# 2024-SS-ZT-1.net
KiCad netlist of a schematic drawn in EasyEDA Pro
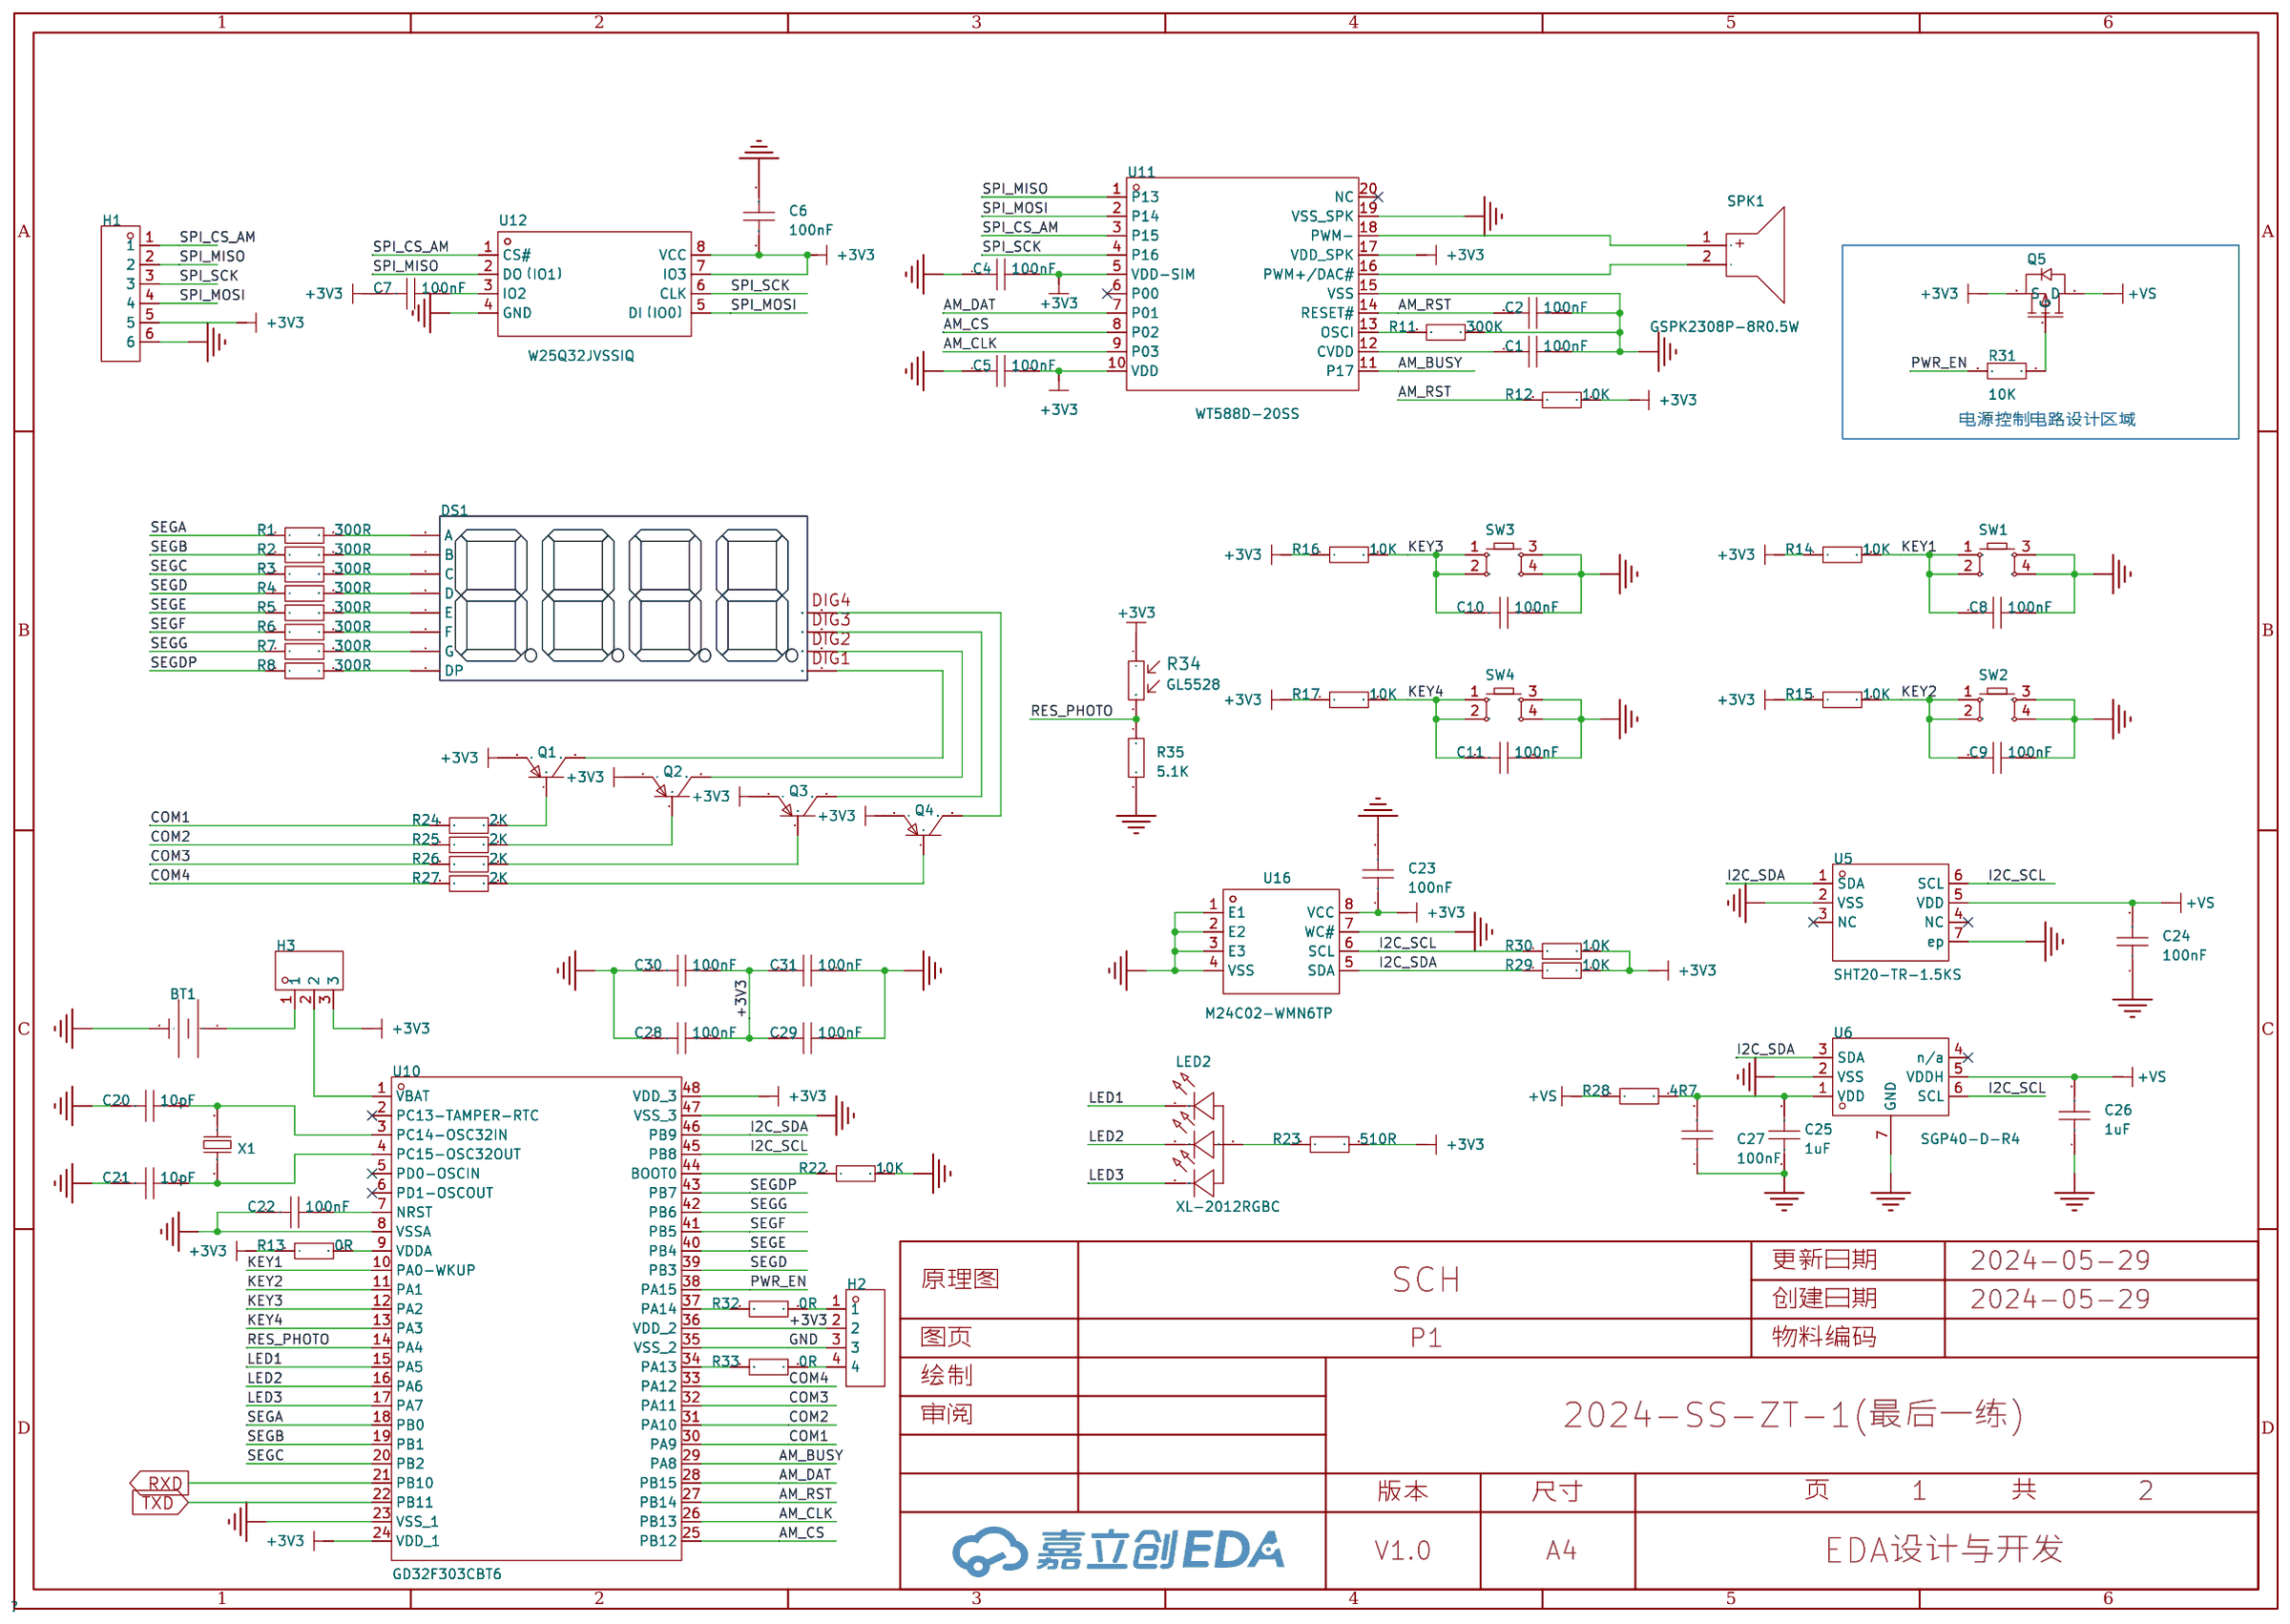
[diagram p0: P1]
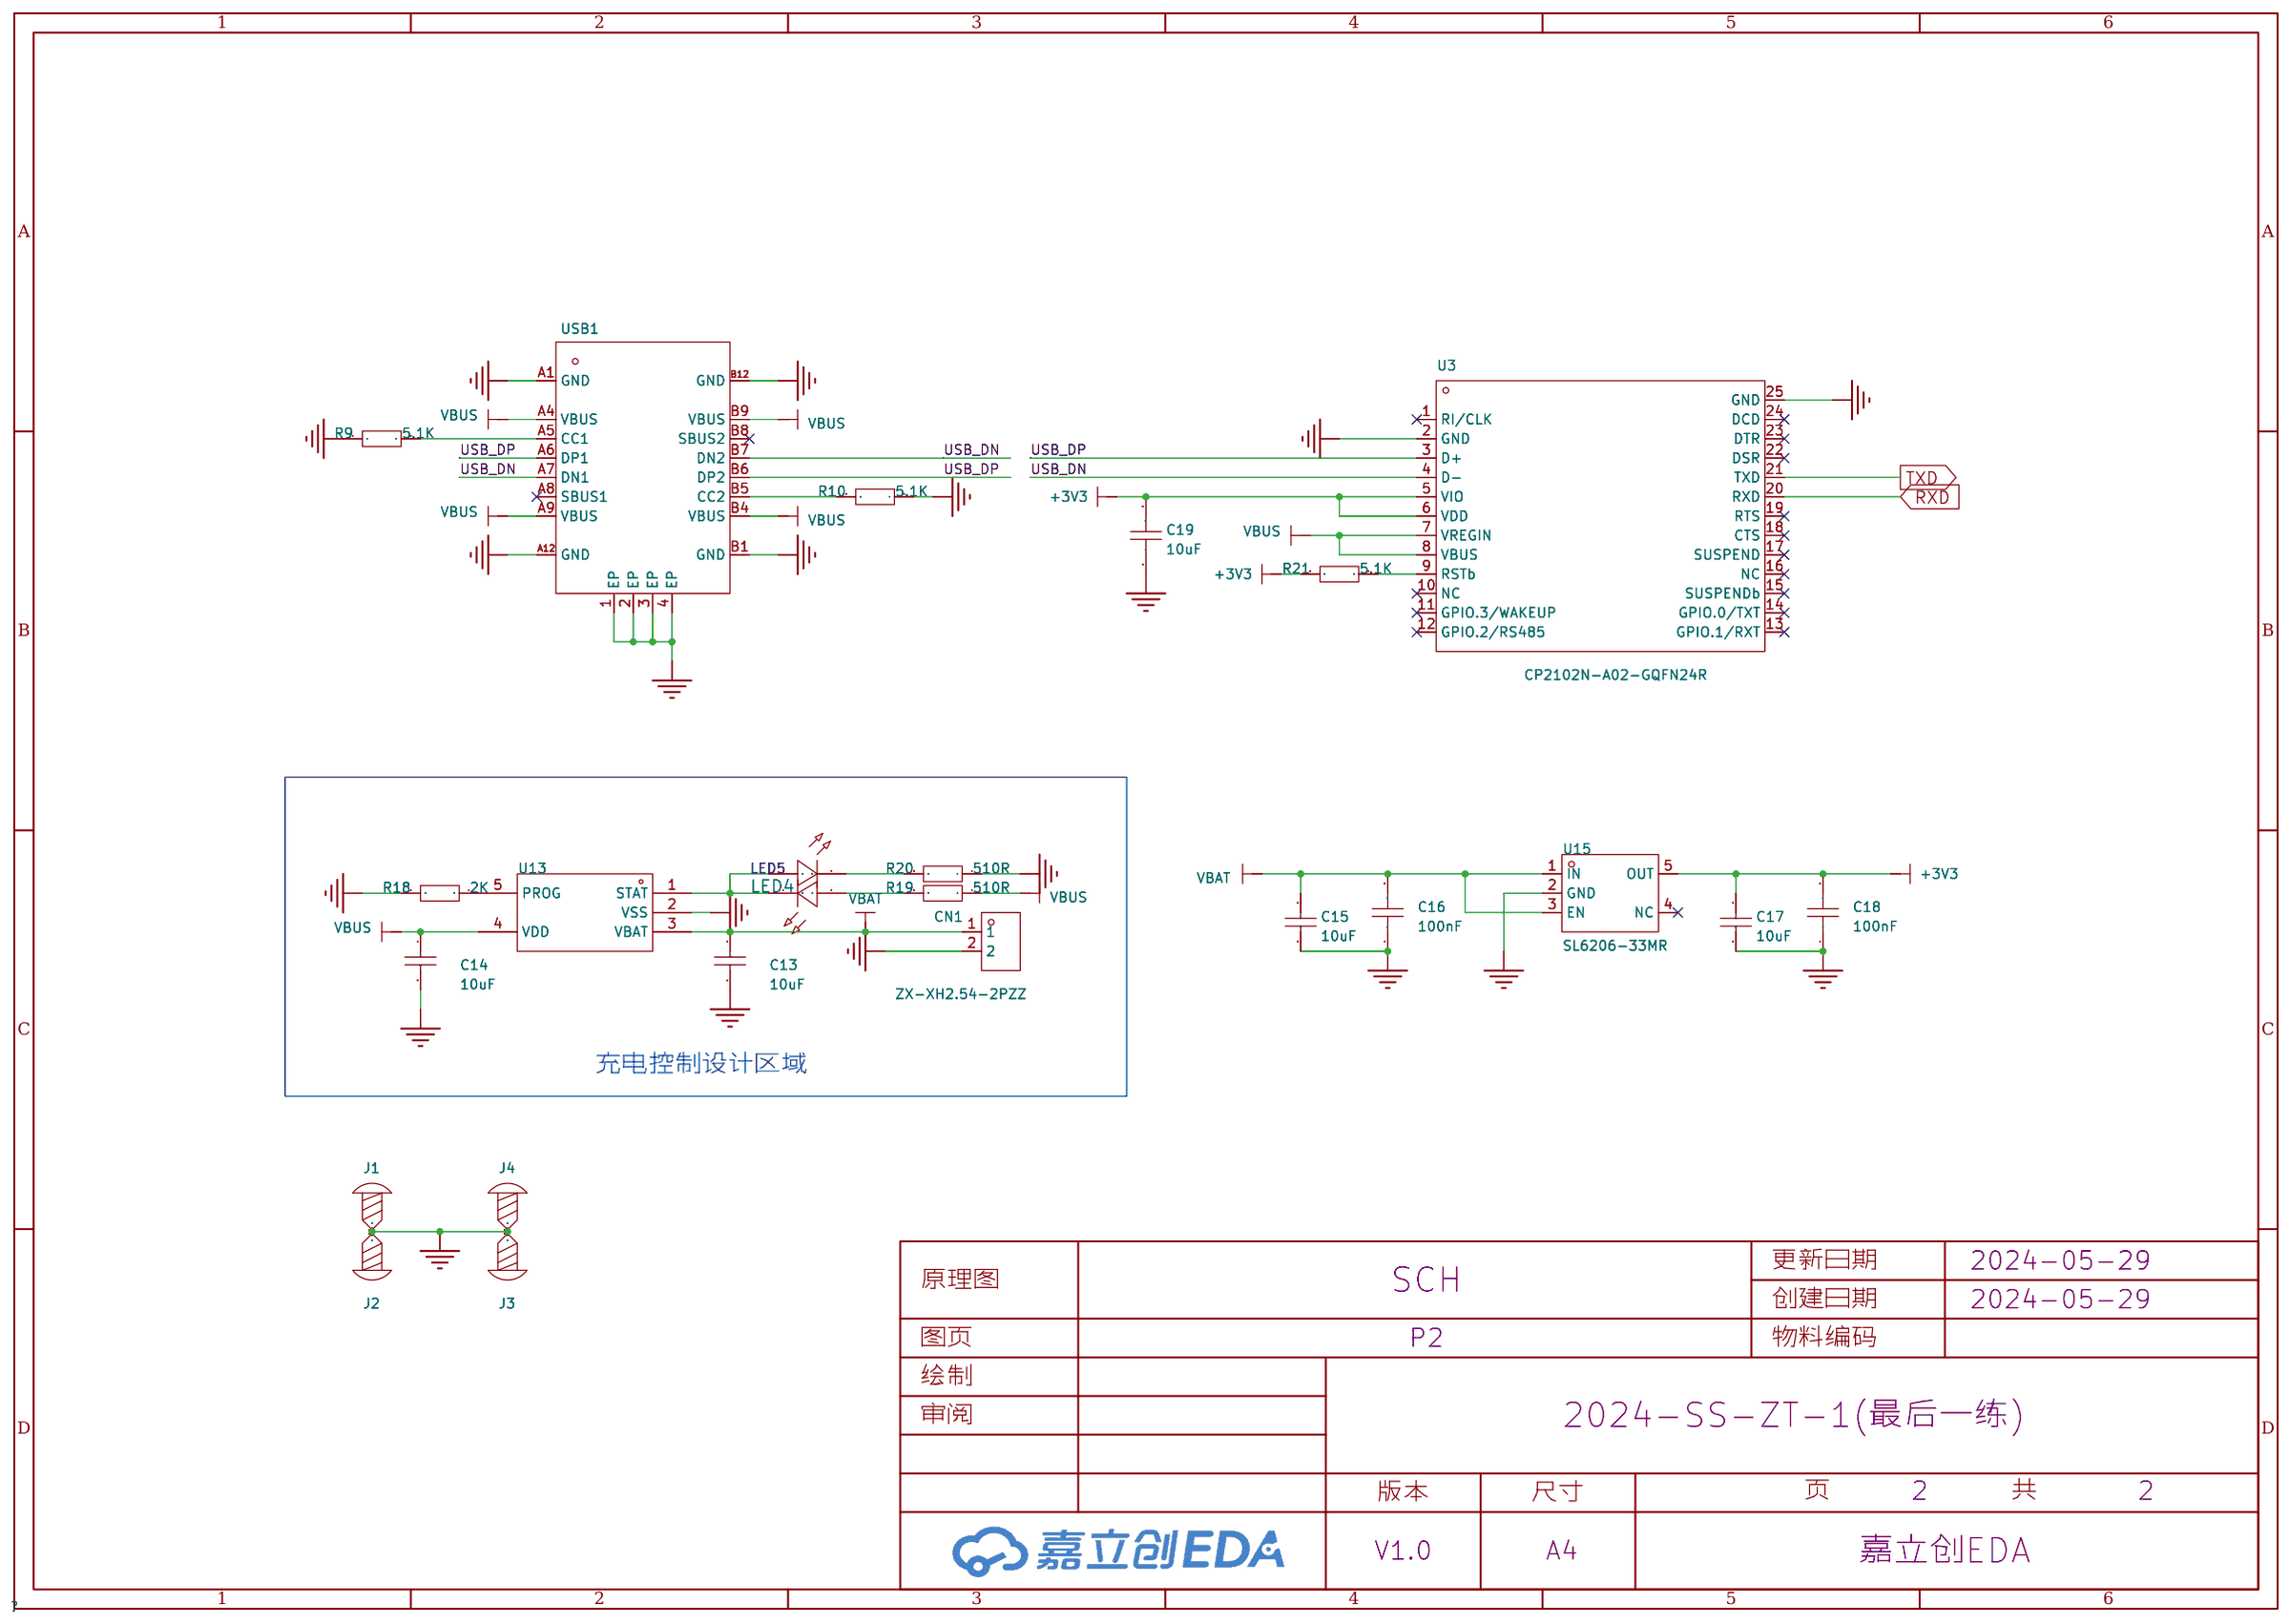
[diagram p1: P2]

(export (version "E")
  (design (tool "Eeschema 10.0.6"))
  (components
    (comp (ref "BT1")
      (value "BS-12-B3AA003")
      (footprint "easyedapro:BAT-SMD_BS-12-B3AA011")
      (description "连接器类型:电池底座;适用电池规格:CR1220;工作温度范围:-25°C~+85°C;")
      (fields (field (name "Manufacturer") "MYOUNG(美阳)"))
      (libsource (lib "easyedapro") (part "BS-12-B3AA003"))
    )
    (comp (ref "C1")
      (value "100nF")
      (footprint "easyedapro:C0805")
      (libsource (lib "easyedapro") (part "CapAcitance"))
    )
    (comp (ref "C2")
      (value "100nF")
      (footprint "easyedapro:C0805")
      (libsource (lib "easyedapro") (part "CapAcitance"))
    )
    (comp (ref "C4")
      (value "100nF")
      (footprint "easyedapro:C0805")
      (libsource (lib "easyedapro") (part "CapAcitance"))
    )
    (comp (ref "C5")
      (value "100nF")
      (footprint "easyedapro:C0805")
      (libsource (lib "easyedapro") (part "CapAcitance"))
    )
    (comp (ref "C6")
      (value "100nF")
      (footprint "easyedapro:C0805")
      (libsource (lib "easyedapro") (part "CapAcitance"))
    )
    (comp (ref "C7")
      (value "100nF")
      (footprint "easyedapro:C0805")
      (libsource (lib "easyedapro") (part "CapAcitance"))
    )
    (comp (ref "C8")
      (value "100nF")
      (footprint "easyedapro:C0805")
      (libsource (lib "easyedapro") (part "CapAcitance"))
    )
    (comp (ref "C9")
      (value "100nF")
      (footprint "easyedapro:C0805")
      (libsource (lib "easyedapro") (part "CapAcitance"))
    )
    (comp (ref "C10")
      (value "100nF")
      (footprint "easyedapro:C0805")
      (libsource (lib "easyedapro") (part "CapAcitance"))
    )
    (comp (ref "C11")
      (value "100nF")
      (footprint "easyedapro:C0805")
      (libsource (lib "easyedapro") (part "CapAcitance"))
    )
    (comp (ref "C20")
      (value "10pF")
      (footprint "easyedapro:C0805")
      (libsource (lib "easyedapro") (part "CapAcitance"))
    )
    (comp (ref "C21")
      (value "10pF")
      (footprint "easyedapro:C0805")
      (libsource (lib "easyedapro") (part "CapAcitance"))
    )
    (comp (ref "C22")
      (value "100nF")
      (footprint "easyedapro:C0805")
      (libsource (lib "easyedapro") (part "CapAcitance"))
    )
    (comp (ref "C23")
      (value "100nF")
      (footprint "easyedapro:C0805")
      (libsource (lib "easyedapro") (part "CapAcitance"))
    )
    (comp (ref "C24")
      (value "100nF")
      (footprint "easyedapro:C0805")
      (libsource (lib "easyedapro") (part "CapAcitance"))
    )
    (comp (ref "C25")
      (value "1uF")
      (footprint "easyedapro:C0805")
      (libsource (lib "easyedapro") (part "CapAcitance"))
    )
    (comp (ref "C26")
      (value "1uF")
      (footprint "easyedapro:C0805")
      (libsource (lib "easyedapro") (part "CapAcitance"))
    )
    (comp (ref "C27")
      (value "100nF")
      (footprint "easyedapro:C0805")
      (libsource (lib "easyedapro") (part "CapAcitance"))
    )
    (comp (ref "C28")
      (value "100nF")
      (footprint "easyedapro:C0805")
      (libsource (lib "easyedapro") (part "CapAcitance"))
    )
    (comp (ref "C29")
      (value "100nF")
      (footprint "easyedapro:C0805")
      (libsource (lib "easyedapro") (part "CapAcitance"))
    )
    (comp (ref "C30")
      (value "100nF")
      (footprint "easyedapro:C0805")
      (libsource (lib "easyedapro") (part "CapAcitance"))
    )
    (comp (ref "C31")
      (value "100nF")
      (footprint "easyedapro:C0805")
      (libsource (lib "easyedapro") (part "CapAcitance"))
    )
    (comp (ref "DS1")
      (value "~")
      (footprint "easyedapro:LED-SEG-TH_FJ5461AH")
      (libsource (lib "easyedapro") (part "LED_SEG_TH_0.56x4"))
    )
    (comp (ref "H1")
      (value "~")
      (footprint "easyedapro:HDR-TH_6P-P2.54-V-F")
      (libsource (lib "easyedapro") (part "Header-Female-2.54_1x6"))
    )
    (comp (ref "H2")
      (value "~")
      (footprint "easyedapro:HDR-TH_4P-P2.54-V-F")
      (libsource (lib "easyedapro") (part "2.54-1*4P母"))
    )
    (comp (ref "H3")
      (value "Jumper3")
      (footprint "easyedapro:HDR-TH_3P-P2.54-V-M-A")
      (libsource (lib "easyedapro") (part "JUMPER3"))
    )
    (comp (ref "LED2")
      (value "XL-2012RGBC")
      (footprint "easyedapro:LED-SMD_4P-L2.0-W1.3-BR")
      (fields (field (name "Manufacturer") "XINGLIGHT(成兴光)"))
      (libsource (lib "easyedapro") (part "XL-2012RGBC"))
    )
    (comp (ref "Q1")
      (value "~")
      (footprint "easyedapro:S8550P_SOT")
      (libsource (lib "easyedapro") (part "PNP"))
    )
    (comp (ref "Q2")
      (value "~")
      (footprint "easyedapro:S8550P_SOT")
      (libsource (lib "easyedapro") (part "PNP"))
    )
    (comp (ref "Q3")
      (value "~")
      (footprint "easyedapro:S8550P_SOT")
      (libsource (lib "easyedapro") (part "PNP"))
    )
    (comp (ref "Q4")
      (value "~")
      (footprint "easyedapro:S8550P_SOT")
      (libsource (lib "easyedapro") (part "PNP"))
    )
    (comp (ref "Q5")
      (value "~")
      (footprint "easyedapro:AO3401A_SOT-23-3")
      (libsource (lib "easyedapro") (part "P_MOS"))
    )
    (comp (ref "R1") (value "300R") (footprint "easyedapro:R0805") (libsource (lib "easyedapro") (part "电阻")))
    (comp (ref "R2") (value "300R") (footprint "easyedapro:R0805") (libsource (lib "easyedapro") (part "电阻")))
    (comp (ref "R3") (value "300R") (footprint "easyedapro:R0805") (libsource (lib "easyedapro") (part "电阻")))
    (comp (ref "R4") (value "300R") (footprint "easyedapro:R0805") (libsource (lib "easyedapro") (part "电阻")))
    (comp (ref "R5") (value "300R") (footprint "easyedapro:R0805") (libsource (lib "easyedapro") (part "电阻")))
    (comp (ref "R6") (value "300R") (footprint "easyedapro:R0805") (libsource (lib "easyedapro") (part "电阻")))
    (comp (ref "R7") (value "300R") (footprint "easyedapro:R0805") (libsource (lib "easyedapro") (part "电阻")))
    (comp (ref "R8") (value "300R") (footprint "easyedapro:R0805") (libsource (lib "easyedapro") (part "电阻")))
    (comp (ref "R11")
      (value "300K")
      (footprint "easyedapro:R0805")
      (libsource (lib "easyedapro") (part "电阻"))
    )
    (comp (ref "R12") (value "10K") (footprint "easyedapro:R0805") (libsource (lib "easyedapro") (part "电阻")))
    (comp (ref "R13") (value "0R") (footprint "easyedapro:R0805") (libsource (lib "easyedapro") (part "电阻")))
    (comp (ref "R14") (value "10K") (footprint "easyedapro:R0805") (libsource (lib "easyedapro") (part "电阻")))
    (comp (ref "R15") (value "10K") (footprint "easyedapro:R0805") (libsource (lib "easyedapro") (part "电阻")))
    (comp (ref "R16") (value "10K") (footprint "easyedapro:R0805") (libsource (lib "easyedapro") (part "电阻")))
    (comp (ref "R17") (value "10K") (footprint "easyedapro:R0805") (libsource (lib "easyedapro") (part "电阻")))
    (comp (ref "R22") (value "10K") (footprint "easyedapro:R0805") (libsource (lib "easyedapro") (part "电阻")))
    (comp (ref "R23")
      (value "510R")
      (footprint "easyedapro:R0805")
      (libsource (lib "easyedapro") (part "电阻"))
    )
    (comp (ref "R24") (value "2K") (footprint "easyedapro:R0805") (libsource (lib "easyedapro") (part "电阻")))
    (comp (ref "R25") (value "2K") (footprint "easyedapro:R0805") (libsource (lib "easyedapro") (part "电阻")))
    (comp (ref "R26") (value "2K") (footprint "easyedapro:R0805") (libsource (lib "easyedapro") (part "电阻")))
    (comp (ref "R27") (value "2K") (footprint "easyedapro:R0805") (libsource (lib "easyedapro") (part "电阻")))
    (comp (ref "R28") (value "4R7") (footprint "easyedapro:R0805") (libsource (lib "easyedapro") (part "电阻")))
    (comp (ref "R29") (value "10K") (footprint "easyedapro:R0805") (libsource (lib "easyedapro") (part "电阻")))
    (comp (ref "R30") (value "10K") (footprint "easyedapro:R0805") (libsource (lib "easyedapro") (part "电阻")))
    (comp (ref "R31") (value "10K") (footprint "easyedapro:R0805") (libsource (lib "easyedapro") (part "电阻")))
    (comp (ref "R32") (value "0R") (footprint "easyedapro:R0805") (libsource (lib "easyedapro") (part "电阻")))
    (comp (ref "R33") (value "0R") (footprint "easyedapro:R0805") (libsource (lib "easyedapro") (part "电阻")))
    (comp (ref "R34")
      (value "GL5528")
      (footprint "easyedapro:RES-TH_L5.1-W4.3-P3.40-D0.5")
      (description "暗电阻:1MΩ;亮电阻 @ 10Lux:8kΩ~20kΩ;光谱峰值(波长):540nm;")
      (fields (field (name "Manufacturer") "森霸"))
      (libsource (lib "easyedapro") (part "GL5528"))
    )
    (comp (ref "R35")
      (value "5.1K")
      (footprint "easyedapro:R0805")
      (libsource (lib "easyedapro") (part "电阻"))
    )
    (comp (ref "SPK1")
      (value "GSPK2308P-8R0.5W")
      (footprint "easyedapro:SPK-TH_BD23.0-P10.00-D0.8-L-RD")
      (fields (field (name "Manufacturer") "INGHAi(赢海)"))
      (libsource (lib "easyedapro") (part "GSPK2308P-8R0.5W"))
    )
    (comp (ref "SW1")
      (value "~")
      (footprint "easyedapro:Key_SMD_12x12x7.3")
      (libsource (lib "easyedapro") (part "轻触按键"))
    )
    (comp (ref "SW2")
      (value "~")
      (footprint "easyedapro:Key_SMD_12x12x7.3")
      (libsource (lib "easyedapro") (part "轻触按键"))
    )
    (comp (ref "SW3")
      (value "~")
      (footprint "easyedapro:Key_SMD_12x12x7.3")
      (libsource (lib "easyedapro") (part "轻触按键"))
    )
    (comp (ref "SW4")
      (value "~")
      (footprint "easyedapro:Key_SMD_12x12x7.3")
      (libsource (lib "easyedapro") (part "轻触按键"))
    )
    (comp (ref "U5")
      (value "SHT20-TR-1.5KS")
      (footprint "easyedapro:DFN-6_L3.0-W3.0-P0.95-TR-EP")
      (description "接口类型:I2C;")
      (fields (field (name "Manufacturer") "Sensirion(瑞士盛思锐)"))
      (libsource (lib "easyedapro") (part "SHT20"))
    )
    (comp (ref "U6")
      (value "SGP40-D-R4")
      (footprint "easyedapro:DFN-6_L2.4-W2.4-P0.80-TL-EP")
      (description "气体类型:空气质量;精度:-;")
      (fields (field (name "Manufacturer") "Sensirion(瑞士盛思锐)"))
      (libsource (lib "easyedapro") (part "SGP40-D-R4"))
    )
    (comp (ref "U10")
      (value "GD32F303CBT6")
      (footprint "easyedapro:LQFP-48_L7.0-W7.0-P0.50-LS9.0-BL")
      (description "CPU内核:CM4;程序存储容量:128KB;RAM总容量:32KB;GPIO端口数量:37;工作电压范围:-;CPU最大主频:120MHz;程序存储器类型:FLASH;")
      (fields (field (name "Manufacturer") "GigaDevice(兆易创新)"))
      (libsource (lib "easyedapro") (part "GD32F303CBT6"))
    )
    (comp (ref "U11")
      (value "WT588D-20SS")
      (footprint "easyedapro:SSOP-20_L7.2-W5.3-P0.65-LS7.8-BL")
      (description "高品质语音芯片")
      (fields (field (name "Manufacturer") "WT(唯创知音)"))
      (libsource (lib "easyedapro") (part "WT588D"))
    )
    (comp (ref "U12")
      (value "W25Q32JVSSIQ")
      (footprint "easyedapro:SOIC-8_L5.3-W5.3-P1.27-LS8.0-BL")
      (description "接口类型:SPI;存储容量:32Mbit;")
      (fields (field (name "Manufacturer") "WINBOND(华邦)"))
      (libsource (lib "easyedapro") (part "W25Q32JVSSIQ"))
    )
    (comp (ref "U16")
      (value "M24C02-WMN6TP")
      (footprint "easyedapro:SOIC-8_L4.9-W3.9-P1.27-LS6.0-BL")
      (description "接口类型:I2C;存储容量:2Kbit;")
      (fields (field (name "Manufacturer") "ST(意法半导体)"))
      (libsource (lib "easyedapro") (part "M24C02-WMN6TP"))
    )
    (comp (ref "X1")
      (value "32.768kHz")
      (footprint "easyedapro:FC-135R_L3.2-W1.5")
      (description "晶振类型:贴片晶振;频率:32.768kHz;常温频差:±20ppm;外接负载电容:12.5pF;")
      (fields (field (name "Manufacturer Part") "Q13FC13500004") (field (name "Manufacturer") "EPSON(爱普生)"))
      (libsource (lib "easyedapro") (part "Q13FC1350000400"))
    )
    (comp (ref "C13")
      (value "10uF")
      (footprint "easyedapro:C1206")
      (description "容值:10uF;精度:±10%;额定电压:50V;材质(温度系数):X5R;")
      (fields
        (field (name "Manufacturer Part") "CL31A106KBHNNNE")
        (field (name "Manufacturer") "SAMSUNG(三星)")
      )
      (libsource (lib "easyedapro") (part "CL31A106KBHNNNE"))
    )
    (comp (ref "C14")
      (value "10uF")
      (footprint "easyedapro:C1206")
      (description "容值:10uF;精度:±10%;额定电压:50V;材质(温度系数):X5R;")
      (fields
        (field (name "Manufacturer Part") "CL31A106KBHNNNE")
        (field (name "Manufacturer") "SAMSUNG(三星)")
      )
      (libsource (lib "easyedapro") (part "CL31A106KBHNNNE"))
    )
    (comp (ref "C15")
      (value "10uF")
      (footprint "easyedapro:C1206")
      (description "容值:10uF;精度:±10%;额定电压:50V;材质(温度系数):X5R;")
      (fields
        (field (name "Manufacturer Part") "CL31A106KBHNNNE")
        (field (name "Manufacturer") "SAMSUNG(三星)")
      )
      (libsource (lib "easyedapro") (part "CL31A106KBHNNNE"))
    )
    (comp (ref "C16")
      (value "100nF")
      (footprint "easyedapro:C0805")
      (libsource (lib "easyedapro") (part "CapAcitance"))
    )
    (comp (ref "C17")
      (value "10uF")
      (footprint "easyedapro:C1206")
      (description "容值:10uF;精度:±10%;额定电压:50V;材质(温度系数):X5R;")
      (fields
        (field (name "Manufacturer Part") "CL31A106KBHNNNE")
        (field (name "Manufacturer") "SAMSUNG(三星)")
      )
      (libsource (lib "easyedapro") (part "CL31A106KBHNNNE"))
    )
    (comp (ref "C18")
      (value "100nF")
      (footprint "easyedapro:C0805")
      (libsource (lib "easyedapro") (part "CapAcitance"))
    )
    (comp (ref "C19")
      (value "10uF")
      (footprint "easyedapro:C0805")
      (libsource (lib "easyedapro") (part "CapAcitance"))
    )
    (comp (ref "CN1")
      (value "ZX-XH2.54-2PZZ")
      (footprint "easyedapro:CONN-TH_2P-P2.50_HX25003-2A")
      (fields (field (name "Manufacturer") "Megastar(兆星)"))
      (libsource (lib "easyedapro") (part "ZX-XH2.54-2PZZ"))
    )
    (comp (ref "J1") (value "~") (footprint "easyedapro:M2螺丝") (libsource (lib "easyedapro") (part "螺丝孔")))
    (comp (ref "J2") (value "~") (footprint "easyedapro:M2螺丝") (libsource (lib "easyedapro") (part "螺丝孔")))
    (comp (ref "J3") (value "~") (footprint "easyedapro:M2螺丝") (libsource (lib "easyedapro") (part "螺丝孔")))
    (comp (ref "J4") (value "~") (footprint "easyedapro:M2螺丝") (libsource (lib "easyedapro") (part "螺丝孔")))
    (comp (ref "LED4")
      (value "~")
      (footprint "easyedapro:LED_0805")
      (libsource (lib "easyedapro") (part "LED_R"))
    )
    (comp (ref "LED5")
      (value "~")
      (footprint "easyedapro:LED_0805")
      (libsource (lib "easyedapro") (part "LED_G"))
    )
    (comp (ref "R9") (value "5.1K") (footprint "easyedapro:R0805") (libsource (lib "easyedapro") (part "电阻")))
    (comp (ref "R10")
      (value "5.1K")
      (footprint "easyedapro:R0805")
      (libsource (lib "easyedapro") (part "电阻"))
    )
    (comp (ref "R18") (value "2K") (footprint "easyedapro:R0805") (libsource (lib "easyedapro") (part "电阻")))
    (comp (ref "R19")
      (value "510R")
      (footprint "easyedapro:R0805")
      (libsource (lib "easyedapro") (part "电阻"))
    )
    (comp (ref "R20")
      (value "510R")
      (footprint "easyedapro:R0805")
      (libsource (lib "easyedapro") (part "电阻"))
    )
    (comp (ref "R21")
      (value "5.1K")
      (footprint "easyedapro:R0805")
      (libsource (lib "easyedapro") (part "电阻"))
    )
    (comp (ref "U3")
      (value "CP2102N-A02-GQFN24R")
      (footprint "easyedapro:QFN-24_L4.0-W4.0-P0.50-TL-EP2.6")
      (description "应用功能:USB转UART;接口协议:UART;")
      (fields (field (name "Manufacturer") "SKYWORKS/SILICON LABS(芯科)"))
      (libsource (lib "easyedapro") (part "CP2102N-A02-GQFN24R"))
    )
    (comp (ref "U13") (value "~") (libsource (lib "easyedapro") (part "BCON")))
    (comp (ref "U15")
      (value "SL6206-33MR")
      (footprint "easyedapro:SOT-23-5_L2.9-W1.6-P0.95-LS2.8-BL")
      (description "输出类型:-;")
      (fields (field (name "Manufacturer") "Slkor(萨科微)"))
      (libsource (lib "easyedapro") (part "SL6206-33MR"))
    )
    (comp (ref "USB1")
      (value "~")
      (footprint "easyedapro:USB_TYPE-C-16P")
      (libsource (lib "easyedapro") (part "USB_TYPE-C-16P"))
    )
  )
  (nets
    (net (code "1") (name "+3V3") (class "Default")
      (node (ref "C17") (pin "2") (pinfunction "2_2") (pintype "input"))
      (node (ref "C18") (pin "2") (pinfunction "2_2") (pintype "input"))
      (node (ref "C19") (pin "2") (pinfunction "2_2") (pintype "input"))
      (node (ref "C23") (pin "1") (pinfunction "1_1") (pintype "input"))
      (node (ref "C28") (pin "1") (pinfunction "1_1") (pintype "input"))
      (node (ref "C29") (pin "2") (pinfunction "2_2") (pintype "input"))
      (node (ref "C30") (pin "1") (pinfunction "1_1") (pintype "input"))
      (node (ref "C31") (pin "2") (pinfunction "2_2") (pintype "input"))
      (node (ref "C4") (pin "2") (pinfunction "2_2") (pintype "input"))
      (node (ref "C5") (pin "2") (pinfunction "2_2") (pintype "input"))
      (node (ref "C6") (pin "2") (pinfunction "2_2") (pintype "input"))
      (node (ref "C7") (pin "1") (pinfunction "1_1") (pintype "input"))
      (node (ref "H1") (pin "5") (pinfunction "5_5") (pintype "unspecified"))
      (node (ref "H2") (pin "2") (pinfunction "2_2") (pintype "unspecified"))
      (node (ref "H3") (pin "3") (pinfunction "3_3") (pintype "input"))
      (node (ref "Q1") (pin "2") (pinfunction "E_2") (pintype "input"))
      (node (ref "Q2") (pin "2") (pinfunction "E_2") (pintype "input"))
      (node (ref "Q3") (pin "2") (pinfunction "E_2") (pintype "input"))
      (node (ref "Q4") (pin "2") (pinfunction "E_2") (pintype "input"))
      (node (ref "Q5") (pin "2") (pinfunction "S_2") (pintype "input"))
      (node (ref "R12") (pin "2") (pinfunction "2_2") (pintype "input"))
      (node (ref "R13") (pin "1") (pinfunction "1_1") (pintype "input"))
      (node (ref "R14") (pin "1") (pinfunction "1_1") (pintype "input"))
      (node (ref "R15") (pin "1") (pinfunction "1_1") (pintype "input"))
      (node (ref "R16") (pin "1") (pinfunction "1_1") (pintype "input"))
      (node (ref "R17") (pin "1") (pinfunction "1_1") (pintype "input"))
      (node (ref "R21") (pin "2") (pinfunction "2_2") (pintype "input"))
      (node (ref "R23") (pin "2") (pinfunction "2_2") (pintype "input"))
      (node (ref "R29") (pin "2") (pinfunction "2_2") (pintype "input"))
      (node (ref "R30") (pin "2") (pinfunction "2_2") (pintype "input"))
      (node (ref "R34") (pin "1") (pinfunction "1_1") (pintype "input"))
      (node (ref "U10") (pin "24") (pinfunction "VDD_1_24") (pintype "unspecified"))
      (node (ref "U10") (pin "36") (pinfunction "VDD_2_36") (pintype "unspecified"))
      (node (ref "U10") (pin "48") (pinfunction "VDD_3_48") (pintype "unspecified"))
      (node (ref "U11") (pin "10") (pinfunction "VDD_10") (pintype "input"))
      (node (ref "U11") (pin "17") (pinfunction "VDD_SPK_17") (pintype "input"))
      (node (ref "U11") (pin "5") (pinfunction "VDD-SIM_5") (pintype "input"))
      (node (ref "U12") (pin "7") (pinfunction "IO3_7") (pintype "unspecified"))
      (node (ref "U12") (pin "8") (pinfunction "VCC_8") (pintype "unspecified"))
      (node (ref "U15") (pin "5") (pinfunction "OUT_5") (pintype "unspecified"))
      (node (ref "U16") (pin "8") (pinfunction "VCC_8") (pintype "unspecified"))
      (node (ref "U3") (pin "5") (pinfunction "VIO_5") (pintype "unspecified"))
      (node (ref "U3") (pin "6") (pinfunction "VDD_6") (pintype "unspecified"))
    )
    (net (code "2") (name "+VS") (class "Default")
      (node (ref "C24") (pin "2") (pinfunction "2_2") (pintype "input"))
      (node (ref "C26") (pin "2") (pinfunction "2_2") (pintype "input"))
      (node (ref "Q5") (pin "3") (pinfunction "D_3") (pintype "input"))
      (node (ref "R28") (pin "1") (pinfunction "1_1") (pintype "input"))
      (node (ref "U5") (pin "5") (pinfunction "VDD_5") (pintype "unspecified"))
      (node (ref "U6") (pin "5") (pinfunction "VDDH_5") (pintype "unspecified"))
    )
    (net (code "3") (name "AM_BUSY") (class "Default")
      (node (ref "U10") (pin "29") (pinfunction "PA8_29") (pintype "unspecified"))
      (node (ref "U11") (pin "11") (pinfunction "P17_11") (pintype "input"))
    )
    (net (code "4") (name "AM_CLK") (class "Default")
      (node (ref "U10") (pin "26") (pinfunction "PB13_26") (pintype "unspecified"))
      (node (ref "U11") (pin "9") (pinfunction "P03_9") (pintype "input"))
    )
    (net (code "5") (name "AM_CS") (class "Default")
      (node (ref "U10") (pin "25") (pinfunction "PB12_25") (pintype "unspecified"))
      (node (ref "U11") (pin "8") (pinfunction "P02_8") (pintype "input"))
    )
    (net (code "6") (name "AM_DAT") (class "Default")
      (node (ref "U10") (pin "28") (pinfunction "PB15_28") (pintype "unspecified"))
      (node (ref "U11") (pin "7") (pinfunction "P01_7") (pintype "input"))
    )
    (net (code "7") (name "AM_RST") (class "Default")
      (node (ref "C2") (pin "1") (pinfunction "1_1") (pintype "input"))
      (node (ref "R12") (pin "1") (pinfunction "1_1") (pintype "input"))
      (node (ref "U10") (pin "27") (pinfunction "PB14_27") (pintype "unspecified"))
      (node (ref "U11") (pin "14") (pinfunction "RESET#_14") (pintype "input"))
    )
    (net (code "8") (name "COM1") (class "Default")
      (node (ref "R24") (pin "1") (pinfunction "1_1") (pintype "input"))
      (node (ref "U10") (pin "30") (pinfunction "PA9_30") (pintype "unspecified"))
    )
    (net (code "9") (name "COM2") (class "Default")
      (node (ref "R25") (pin "1") (pinfunction "1_1") (pintype "input"))
      (node (ref "U10") (pin "31") (pinfunction "PA10_31") (pintype "unspecified"))
    )
    (net (code "10") (name "COM3") (class "Default")
      (node (ref "R26") (pin "1") (pinfunction "1_1") (pintype "input"))
      (node (ref "U10") (pin "32") (pinfunction "PA11_32") (pintype "unspecified"))
    )
    (net (code "11") (name "COM4") (class "Default")
      (node (ref "R27") (pin "1") (pinfunction "1_1") (pintype "input"))
      (node (ref "U10") (pin "33") (pinfunction "PA12_33") (pintype "unspecified"))
    )
    (net (code "12") (name "GND") (class "Default")
      (node (ref "BT1") (pin "2") (pinfunction "-_2") (pintype "unspecified"))
      (node (ref "C1") (pin "2") (pinfunction "2_2") (pintype "input"))
      (node (ref "C10") (pin "2") (pinfunction "2_2") (pintype "input"))
      (node (ref "C11") (pin "2") (pinfunction "2_2") (pintype "input"))
      (node (ref "C13") (pin "2") (pinfunction "2_2") (pintype "input"))
      (node (ref "C14") (pin "2") (pinfunction "2_2") (pintype "input"))
      (node (ref "C15") (pin "1") (pinfunction "1_1") (pintype "input"))
      (node (ref "C16") (pin "1") (pinfunction "1_1") (pintype "input"))
      (node (ref "C17") (pin "1") (pinfunction "1_1") (pintype "input"))
      (node (ref "C18") (pin "1") (pinfunction "1_1") (pintype "input"))
      (node (ref "C19") (pin "1") (pinfunction "1_1") (pintype "input"))
      (node (ref "C2") (pin "2") (pinfunction "2_2") (pintype "input"))
      (node (ref "C20") (pin "1") (pinfunction "1_1") (pintype "input"))
      (node (ref "C21") (pin "1") (pinfunction "1_1") (pintype "input"))
      (node (ref "C22") (pin "1") (pinfunction "1_1") (pintype "input"))
      (node (ref "C23") (pin "2") (pinfunction "2_2") (pintype "input"))
      (node (ref "C24") (pin "1") (pinfunction "1_1") (pintype "input"))
      (node (ref "C25") (pin "1") (pinfunction "1_1") (pintype "input"))
      (node (ref "C26") (pin "1") (pinfunction "1_1") (pintype "input"))
      (node (ref "C27") (pin "1") (pinfunction "1_1") (pintype "input"))
      (node (ref "C28") (pin "2") (pinfunction "2_2") (pintype "input"))
      (node (ref "C29") (pin "1") (pinfunction "1_1") (pintype "input"))
      (node (ref "C30") (pin "2") (pinfunction "2_2") (pintype "input"))
      (node (ref "C31") (pin "1") (pinfunction "1_1") (pintype "input"))
      (node (ref "C4") (pin "1") (pinfunction "1_1") (pintype "input"))
      (node (ref "C5") (pin "1") (pinfunction "1_1") (pintype "input"))
      (node (ref "C6") (pin "1") (pinfunction "1_1") (pintype "input"))
      (node (ref "C8") (pin "2") (pinfunction "2_2") (pintype "input"))
      (node (ref "C9") (pin "2") (pinfunction "2_2") (pintype "input"))
      (node (ref "CN1") (pin "2") (pinfunction "2_2") (pintype "unspecified"))
      (node (ref "H1") (pin "6") (pinfunction "6_6") (pintype "unspecified"))
      (node (ref "H2") (pin "3") (pinfunction "3_3") (pintype "unspecified"))
      (node (ref "J1") (pin "1") (pinfunction "1_1") (pintype "input"))
      (node (ref "J2") (pin "1") (pinfunction "1_1") (pintype "input"))
      (node (ref "J3") (pin "1") (pinfunction "1_1") (pintype "input"))
      (node (ref "J4") (pin "1") (pinfunction "1_1") (pintype "input"))
      (node (ref "R10") (pin "1") (pinfunction "1_1") (pintype "input"))
      (node (ref "R11") (pin "2") (pinfunction "2_2") (pintype "input"))
      (node (ref "R18") (pin "2") (pinfunction "2_2") (pintype "input"))
      (node (ref "R20") (pin "1") (pinfunction "1_1") (pintype "input"))
      (node (ref "R22") (pin "2") (pinfunction "2_2") (pintype "input"))
      (node (ref "R35") (pin "2") (pinfunction "2_2") (pintype "input"))
      (node (ref "R9") (pin "1") (pinfunction "1_1") (pintype "input"))
      (node (ref "SW1") (pin "3") (pinfunction "3_3") (pintype "input"))
      (node (ref "SW1") (pin "4") (pinfunction "4_4") (pintype "input"))
      (node (ref "SW2") (pin "3") (pinfunction "3_3") (pintype "input"))
      (node (ref "SW2") (pin "4") (pinfunction "4_4") (pintype "input"))
      (node (ref "SW3") (pin "3") (pinfunction "3_3") (pintype "input"))
      (node (ref "SW3") (pin "4") (pinfunction "4_4") (pintype "input"))
      (node (ref "SW4") (pin "3") (pinfunction "3_3") (pintype "input"))
      (node (ref "SW4") (pin "4") (pinfunction "4_4") (pintype "input"))
      (node (ref "U10") (pin "23") (pinfunction "VSS_1_23") (pintype "unspecified"))
      (node (ref "U10") (pin "35") (pinfunction "VSS_2_35") (pintype "unspecified"))
      (node (ref "U10") (pin "47") (pinfunction "VSS_3_47") (pintype "unspecified"))
      (node (ref "U10") (pin "8") (pinfunction "VSSA_8") (pintype "unspecified"))
      (node (ref "U11") (pin "15") (pinfunction "VSS_15") (pintype "input"))
      (node (ref "U11") (pin "19") (pinfunction "VSS_SPK_19") (pintype "input"))
      (node (ref "U12") (pin "4") (pinfunction "GND_4") (pintype "unspecified"))
      (node (ref "U13") (pin "2") (pinfunction "VSS_2") (pintype "input"))
      (node (ref "U15") (pin "2") (pinfunction "GND_2") (pintype "unspecified"))
      (node (ref "U16") (pin "1") (pinfunction "E1_1") (pintype "unspecified"))
      (node (ref "U16") (pin "2") (pinfunction "E2_2") (pintype "unspecified"))
      (node (ref "U16") (pin "3") (pinfunction "E3_3") (pintype "unspecified"))
      (node (ref "U16") (pin "4") (pinfunction "VSS_4") (pintype "unspecified"))
      (node (ref "U16") (pin "7") (pinfunction "WC#_7") (pintype "unspecified"))
      (node (ref "U3") (pin "2") (pinfunction "GND_2") (pintype "unspecified"))
      (node (ref "U3") (pin "25") (pinfunction "GND_25") (pintype "unspecified"))
      (node (ref "U5") (pin "2") (pinfunction "VSS_2") (pintype "unspecified"))
      (node (ref "U5") (pin "7") (pinfunction "ep_7") (pintype "unspecified"))
      (node (ref "U6") (pin "2") (pinfunction "VSS_2") (pintype "unspecified"))
      (node (ref "U6") (pin "7") (pinfunction "GND_7") (pintype "unspecified"))
      (node (ref "USB1") (pin "1") (pinfunction "EP_1") (pintype "input"))
      (node (ref "USB1") (pin "2") (pinfunction "EP_2") (pintype "input"))
      (node (ref "USB1") (pin "3") (pinfunction "EP_3") (pintype "input"))
      (node (ref "USB1") (pin "4") (pinfunction "EP_4") (pintype "input"))
      (node (ref "USB1") (pin "A1") (pinfunction "GND_A1") (pintype "input"))
      (node (ref "USB1") (pin "A12") (pinfunction "GND_A12") (pintype "input"))
      (node (ref "USB1") (pin "B1") (pinfunction "GND_B1") (pintype "input"))
      (node (ref "USB1") (pin "B12") (pinfunction "GND_B12") (pintype "input"))
    )
    (net (code "13") (name "I2C_SCL") (class "Default")
      (node (ref "R30") (pin "1") (pinfunction "1_1") (pintype "input"))
      (node (ref "U10") (pin "45") (pinfunction "PB8_45") (pintype "unspecified"))
      (node (ref "U16") (pin "6") (pinfunction "SCL_6") (pintype "unspecified"))
      (node (ref "U5") (pin "6") (pinfunction "SCL_6") (pintype "unspecified"))
      (node (ref "U6") (pin "6") (pinfunction "SCL_6") (pintype "unspecified"))
    )
    (net (code "14") (name "I2C_SDA") (class "Default")
      (node (ref "R29") (pin "1") (pinfunction "1_1") (pintype "input"))
      (node (ref "U10") (pin "46") (pinfunction "PB9_46") (pintype "unspecified"))
      (node (ref "U16") (pin "5") (pinfunction "SDA_5") (pintype "unspecified"))
      (node (ref "U5") (pin "1") (pinfunction "SDA_1") (pintype "unspecified"))
      (node (ref "U6") (pin "3") (pinfunction "SDA_3") (pintype "unspecified"))
    )
    (net (code "15") (name "KEY1") (class "Default")
      (node (ref "C8") (pin "1") (pinfunction "1_1") (pintype "input"))
      (node (ref "R14") (pin "2") (pinfunction "2_2") (pintype "input"))
      (node (ref "SW1") (pin "1") (pinfunction "1_1") (pintype "input"))
      (node (ref "SW1") (pin "2") (pinfunction "2_2") (pintype "input"))
      (node (ref "U10") (pin "10") (pinfunction "PA0-WKUP_10") (pintype "unspecified"))
    )
    (net (code "16") (name "KEY2") (class "Default")
      (node (ref "C9") (pin "1") (pinfunction "1_1") (pintype "input"))
      (node (ref "R15") (pin "2") (pinfunction "2_2") (pintype "input"))
      (node (ref "SW2") (pin "1") (pinfunction "1_1") (pintype "input"))
      (node (ref "SW2") (pin "2") (pinfunction "2_2") (pintype "input"))
      (node (ref "U10") (pin "11") (pinfunction "PA1_11") (pintype "unspecified"))
    )
    (net (code "17") (name "KEY3") (class "Default")
      (node (ref "C10") (pin "1") (pinfunction "1_1") (pintype "input"))
      (node (ref "R16") (pin "2") (pinfunction "2_2") (pintype "input"))
      (node (ref "SW3") (pin "1") (pinfunction "1_1") (pintype "input"))
      (node (ref "SW3") (pin "2") (pinfunction "2_2") (pintype "input"))
      (node (ref "U10") (pin "12") (pinfunction "PA2_12") (pintype "unspecified"))
    )
    (net (code "18") (name "KEY4") (class "Default")
      (node (ref "C11") (pin "1") (pinfunction "1_1") (pintype "input"))
      (node (ref "R17") (pin "2") (pinfunction "2_2") (pintype "input"))
      (node (ref "SW4") (pin "1") (pinfunction "1_1") (pintype "input"))
      (node (ref "SW4") (pin "2") (pinfunction "2_2") (pintype "input"))
      (node (ref "U10") (pin "13") (pinfunction "PA3_13") (pintype "unspecified"))
    )
    (net (code "19") (name "LED1") (class "Default")
      (node (ref "LED2") (pin "1") (pinfunction "1_1") (pintype "unspecified"))
      (node (ref "U10") (pin "15") (pinfunction "PA5_15") (pintype "unspecified"))
    )
    (net (code "20") (name "LED2") (class "Default")
      (node (ref "LED2") (pin "2") (pinfunction "2_2") (pintype "unspecified"))
      (node (ref "U10") (pin "16") (pinfunction "PA6_16") (pintype "unspecified"))
    )
    (net (code "21") (name "LED3") (class "Default")
      (node (ref "LED2") (pin "4") (pinfunction "4_4") (pintype "unspecified"))
      (node (ref "U10") (pin "17") (pinfunction "PA7_17") (pintype "unspecified"))
    )
    (net (code "22") (name "Net-(BT1-+)") (class "Default")
      (node (ref "BT1") (pin "1") (pinfunction "+_1") (pintype "unspecified"))
      (node (ref "H3") (pin "1") (pinfunction "1_1") (pintype "input"))
    )
    (net (code "23") (name "Net-(DS1-A)") (class "Default")
      (node (ref "DS1") (pin "11") (pinfunction "A_11") (pintype "input"))
      (node (ref "R1") (pin "2") (pinfunction "2_2") (pintype "input"))
    )
    (net (code "24") (name "Net-(DS1-B)") (class "Default")
      (node (ref "DS1") (pin "7") (pinfunction "B_7") (pintype "input"))
      (node (ref "R2") (pin "2") (pinfunction "2_2") (pintype "input"))
    )
    (net (code "25") (name "Net-(DS1-C)") (class "Default")
      (node (ref "DS1") (pin "4") (pinfunction "C_4") (pintype "input"))
      (node (ref "R3") (pin "2") (pinfunction "2_2") (pintype "input"))
    )
    (net (code "26") (name "Net-(DS1-D)") (class "Default")
      (node (ref "DS1") (pin "2") (pinfunction "D_2") (pintype "input"))
      (node (ref "R4") (pin "2") (pinfunction "2_2") (pintype "input"))
    )
    (net (code "27") (name "Net-(DS1-DIG1)") (class "Default")
      (node (ref "DS1") (pin "12") (pinfunction "DIG1_12") (pintype "input"))
      (node (ref "Q1") (pin "3") (pinfunction "C_3") (pintype "input"))
    )
    (net (code "28") (name "Net-(DS1-DIG2)") (class "Default")
      (node (ref "DS1") (pin "9") (pinfunction "DIG2_9") (pintype "input"))
      (node (ref "Q2") (pin "3") (pinfunction "C_3") (pintype "input"))
    )
    (net (code "29") (name "Net-(DS1-DIG3)") (class "Default")
      (node (ref "DS1") (pin "8") (pinfunction "DIG3_8") (pintype "input"))
      (node (ref "Q3") (pin "3") (pinfunction "C_3") (pintype "input"))
    )
    (net (code "30") (name "Net-(DS1-DIG4)") (class "Default")
      (node (ref "DS1") (pin "6") (pinfunction "DIG4_6") (pintype "input"))
      (node (ref "Q4") (pin "3") (pinfunction "C_3") (pintype "input"))
    )
    (net (code "31") (name "Net-(DS1-DP)") (class "Default")
      (node (ref "DS1") (pin "3") (pinfunction "DP_3") (pintype "input"))
      (node (ref "R8") (pin "2") (pinfunction "2_2") (pintype "input"))
    )
    (net (code "32") (name "Net-(DS1-E)") (class "Default")
      (node (ref "DS1") (pin "1") (pinfunction "E_1") (pintype "input"))
      (node (ref "R5") (pin "2") (pinfunction "2_2") (pintype "input"))
    )
    (net (code "33") (name "Net-(DS1-F)") (class "Default")
      (node (ref "DS1") (pin "10") (pinfunction "F_10") (pintype "input"))
      (node (ref "R6") (pin "2") (pinfunction "2_2") (pintype "input"))
    )
    (net (code "34") (name "Net-(DS1-G)") (class "Default")
      (node (ref "DS1") (pin "5") (pinfunction "G_5") (pintype "input"))
      (node (ref "R7") (pin "2") (pinfunction "2_2") (pintype "input"))
    )
    (net (code "35") (name "Net-(H2-Pad1)") (class "Default")
      (node (ref "H2") (pin "1") (pinfunction "1_1") (pintype "unspecified"))
      (node (ref "R32") (pin "2") (pinfunction "2_2") (pintype "input"))
    )
    (net (code "36") (name "Net-(H2-Pad4)") (class "Default")
      (node (ref "H2") (pin "4") (pinfunction "4_4") (pintype "unspecified"))
      (node (ref "R33") (pin "2") (pinfunction "2_2") (pintype "input"))
    )
    (net (code "37") (name "Net-(LED2-Pad3)") (class "Default")
      (node (ref "LED2") (pin "3") (pinfunction "3_3") (pintype "unspecified"))
      (node (ref "R23") (pin "1") (pinfunction "1_1") (pintype "input"))
    )
    (net (code "38") (name "Net-(LED4-A)") (class "Default")
      (node (ref "LED4") (pin "2") (pinfunction "A_2") (pintype "input"))
      (node (ref "R19") (pin "2") (pinfunction "2_2") (pintype "input"))
    )
    (net (code "39") (name "Net-(LED4-C)") (class "Default")
      (node (ref "LED4") (pin "1") (pinfunction "C_1") (pintype "input"))
      (node (ref "LED5") (pin "2") (pinfunction "A_2") (pintype "input"))
      (node (ref "U13") (pin "1") (pinfunction "STAT_1") (pintype "input"))
    )
    (net (code "40") (name "Net-(LED5-C)") (class "Default")
      (node (ref "LED5") (pin "1") (pinfunction "C_1") (pintype "input"))
      (node (ref "R20") (pin "2") (pinfunction "2_2") (pintype "input"))
    )
    (net (code "41") (name "Net-(Q1-B)") (class "Default")
      (node (ref "Q1") (pin "1") (pinfunction "B_1") (pintype "input"))
      (node (ref "R24") (pin "2") (pinfunction "2_2") (pintype "input"))
    )
    (net (code "42") (name "Net-(Q2-B)") (class "Default")
      (node (ref "Q2") (pin "1") (pinfunction "B_1") (pintype "input"))
      (node (ref "R25") (pin "2") (pinfunction "2_2") (pintype "input"))
    )
    (net (code "43") (name "Net-(Q3-B)") (class "Default")
      (node (ref "Q3") (pin "1") (pinfunction "B_1") (pintype "input"))
      (node (ref "R26") (pin "2") (pinfunction "2_2") (pintype "input"))
    )
    (net (code "44") (name "Net-(Q4-B)") (class "Default")
      (node (ref "Q4") (pin "1") (pinfunction "B_1") (pintype "input"))
      (node (ref "R27") (pin "2") (pinfunction "2_2") (pintype "input"))
    )
    (net (code "45") (name "Net-(Q5-G)") (class "Default")
      (node (ref "Q5") (pin "1") (pinfunction "G_1") (pintype "input"))
      (node (ref "R31") (pin "1") (pinfunction "1_1") (pintype "input"))
    )
    (net (code "46") (name "Net-(SPK1-+)") (class "Default")
      (node (ref "SPK1") (pin "1") (pinfunction "+_1") (pintype "input"))
      (node (ref "U11") (pin "18") (pinfunction "PWM-_18") (pintype "input"))
    )
    (net (code "47") (name "Net-(SPK1--)") (class "Default")
      (node (ref "SPK1") (pin "2") (pinfunction "-_2") (pintype "input"))
      (node (ref "U11") (pin "16") (pinfunction "PWM+/DAC#_16") (pintype "input"))
    )
    (net (code "48") (name "Net-(U3-RSTb)") (class "Default")
      (node (ref "R21") (pin "1") (pinfunction "1_1") (pintype "input"))
      (node (ref "U3") (pin "9") (pinfunction "RSTb_9") (pintype "unspecified"))
    )
    (net (code "49") (name "Net-(U6-VDD)") (class "Default")
      (node (ref "C25") (pin "2") (pinfunction "2_2") (pintype "input"))
      (node (ref "C27") (pin "2") (pinfunction "2_2") (pintype "input"))
      (node (ref "R28") (pin "2") (pinfunction "2_2") (pintype "input"))
      (node (ref "U6") (pin "1") (pinfunction "VDD_1") (pintype "unspecified"))
    )
    (net (code "50") (name "Net-(U10-BOOT0)") (class "Default")
      (node (ref "R22") (pin "1") (pinfunction "1_1") (pintype "input"))
      (node (ref "U10") (pin "44") (pinfunction "BOOT0_44") (pintype "unspecified"))
    )
    (net (code "51") (name "Net-(U10-NRST)") (class "Default")
      (node (ref "C22") (pin "2") (pinfunction "2_2") (pintype "input"))
      (node (ref "U10") (pin "7") (pinfunction "NRST_7") (pintype "unspecified"))
    )
    (net (code "52") (name "Net-(U10-PA13)") (class "Default")
      (node (ref "R33") (pin "1") (pinfunction "1_1") (pintype "input"))
      (node (ref "U10") (pin "34") (pinfunction "PA13_34") (pintype "unspecified"))
    )
    (net (code "53") (name "Net-(U10-PA14)") (class "Default")
      (node (ref "R32") (pin "1") (pinfunction "1_1") (pintype "input"))
      (node (ref "U10") (pin "37") (pinfunction "PA14_37") (pintype "unspecified"))
    )
    (net (code "54") (name "Net-(U10-PC14-OSC32IN)") (class "Default")
      (node (ref "C20") (pin "2") (pinfunction "2_2") (pintype "input"))
      (node (ref "U10") (pin "3") (pinfunction "PC14-OSC32IN_3") (pintype "unspecified"))
      (node (ref "X1") (pin "1") (pinfunction "1_1") (pintype "unspecified"))
    )
    (net (code "55") (name "Net-(U10-PC15-OSC32OUT)") (class "Default")
      (node (ref "C21") (pin "2") (pinfunction "2_2") (pintype "input"))
      (node (ref "U10") (pin "4") (pinfunction "PC15-OSC32OUT_4") (pintype "unspecified"))
      (node (ref "X1") (pin "2") (pinfunction "2_2") (pintype "unspecified"))
    )
    (net (code "56") (name "Net-(U10-VBAT)") (class "Default")
      (node (ref "H3") (pin "2") (pinfunction "2_2") (pintype "input"))
      (node (ref "U10") (pin "1") (pinfunction "VBAT_1") (pintype "unspecified"))
    )
    (net (code "57") (name "Net-(U10-VDDA)") (class "Default")
      (node (ref "R13") (pin "2") (pinfunction "2_2") (pintype "input"))
      (node (ref "U10") (pin "9") (pinfunction "VDDA_9") (pintype "unspecified"))
    )
    (net (code "58") (name "Net-(U11-CVDD)") (class "Default")
      (node (ref "C1") (pin "1") (pinfunction "1_1") (pintype "input"))
      (node (ref "U11") (pin "12") (pinfunction "CVDD_12") (pintype "input"))
    )
    (net (code "59") (name "Net-(U11-OSCI)") (class "Default")
      (node (ref "R11") (pin "1") (pinfunction "1_1") (pintype "input"))
      (node (ref "U11") (pin "13") (pinfunction "OSCI_13") (pintype "input"))
    )
    (net (code "60") (name "Net-(U12-IO2)") (class "Default")
      (node (ref "C7") (pin "2") (pinfunction "2_2") (pintype "input"))
      (node (ref "U12") (pin "3") (pinfunction "IO2_3") (pintype "unspecified"))
    )
    (net (code "61") (name "Net-(U13-PROG)") (class "Default")
      (node (ref "R18") (pin "1") (pinfunction "1_1") (pintype "input"))
      (node (ref "U13") (pin "5") (pinfunction "PROG_5") (pintype "input"))
    )
    (net (code "62") (name "Net-(USB1-CC1)") (class "Default")
      (node (ref "R9") (pin "2") (pinfunction "2_2") (pintype "input"))
      (node (ref "USB1") (pin "A5") (pinfunction "CC1_A5") (pintype "input"))
    )
    (net (code "63") (name "Net-(USB1-CC2)") (class "Default")
      (node (ref "R10") (pin "2") (pinfunction "2_2") (pintype "input"))
      (node (ref "USB1") (pin "B5") (pinfunction "CC2_B5") (pintype "input"))
    )
    (net (code "64") (name "PWR_EN") (class "Default")
      (node (ref "R31") (pin "2") (pinfunction "2_2") (pintype "input"))
      (node (ref "U10") (pin "38") (pinfunction "PA15_38") (pintype "unspecified"))
    )
    (net (code "65") (name "RES_PHOTO") (class "Default")
      (node (ref "R34") (pin "2") (pinfunction "2_2") (pintype "input"))
      (node (ref "R35") (pin "1") (pinfunction "1_1") (pintype "input"))
      (node (ref "U10") (pin "14") (pinfunction "PA4_14") (pintype "unspecified"))
    )
    (net (code "66") (name "RXD") (class "Default")
      (node (ref "U10") (pin "21") (pinfunction "PB10_21") (pintype "unspecified"))
      (node (ref "U3") (pin "20") (pinfunction "RXD_20") (pintype "unspecified"))
    )
    (net (code "67") (name "SEGA") (class "Default")
      (node (ref "R1") (pin "1") (pinfunction "1_1") (pintype "input"))
      (node (ref "U10") (pin "18") (pinfunction "PB0_18") (pintype "unspecified"))
    )
    (net (code "68") (name "SEGB") (class "Default")
      (node (ref "R2") (pin "1") (pinfunction "1_1") (pintype "input"))
      (node (ref "U10") (pin "19") (pinfunction "PB1_19") (pintype "unspecified"))
    )
    (net (code "69") (name "SEGC") (class "Default")
      (node (ref "R3") (pin "1") (pinfunction "1_1") (pintype "input"))
      (node (ref "U10") (pin "20") (pinfunction "PB2_20") (pintype "unspecified"))
    )
    (net (code "70") (name "SEGD") (class "Default")
      (node (ref "R4") (pin "1") (pinfunction "1_1") (pintype "input"))
      (node (ref "U10") (pin "39") (pinfunction "PB3_39") (pintype "unspecified"))
    )
    (net (code "71") (name "SEGDP") (class "Default")
      (node (ref "R8") (pin "1") (pinfunction "1_1") (pintype "input"))
      (node (ref "U10") (pin "43") (pinfunction "PB7_43") (pintype "unspecified"))
    )
    (net (code "72") (name "SEGE") (class "Default")
      (node (ref "R5") (pin "1") (pinfunction "1_1") (pintype "input"))
      (node (ref "U10") (pin "40") (pinfunction "PB4_40") (pintype "unspecified"))
    )
    (net (code "73") (name "SEGF") (class "Default")
      (node (ref "R6") (pin "1") (pinfunction "1_1") (pintype "input"))
      (node (ref "U10") (pin "41") (pinfunction "PB5_41") (pintype "unspecified"))
    )
    (net (code "74") (name "SEGG") (class "Default")
      (node (ref "R7") (pin "1") (pinfunction "1_1") (pintype "input"))
      (node (ref "U10") (pin "42") (pinfunction "PB6_42") (pintype "unspecified"))
    )
    (net (code "75") (name "SPI_CS_AM") (class "Default")
      (node (ref "H1") (pin "1") (pinfunction "1_1") (pintype "unspecified"))
      (node (ref "U11") (pin "3") (pinfunction "P15_3") (pintype "input"))
      (node (ref "U12") (pin "1") (pinfunction "CS#_1") (pintype "unspecified"))
    )
    (net (code "76") (name "SPI_MISO") (class "Default")
      (node (ref "H1") (pin "2") (pinfunction "2_2") (pintype "unspecified"))
      (node (ref "U11") (pin "1") (pinfunction "P13_1") (pintype "input"))
      (node (ref "U12") (pin "2") (pinfunction "DO（IO1）_2") (pintype "unspecified"))
    )
    (net (code "77") (name "SPI_MOSI") (class "Default")
      (node (ref "H1") (pin "4") (pinfunction "4_4") (pintype "unspecified"))
      (node (ref "U11") (pin "2") (pinfunction "P14_2") (pintype "input"))
      (node (ref "U12") (pin "5") (pinfunction "DI（IO0）_5") (pintype "unspecified"))
    )
    (net (code "78") (name "SPI_SCK") (class "Default")
      (node (ref "H1") (pin "3") (pinfunction "3_3") (pintype "unspecified"))
      (node (ref "U11") (pin "4") (pinfunction "P16_4") (pintype "input"))
      (node (ref "U12") (pin "6") (pinfunction "CLK_6") (pintype "unspecified"))
    )
    (net (code "79") (name "TXD") (class "Default")
      (node (ref "U10") (pin "22") (pinfunction "PB11_22") (pintype "unspecified"))
      (node (ref "U3") (pin "21") (pinfunction "TXD_21") (pintype "unspecified"))
    )
    (net (code "80") (name "USB_DN") (class "Default")
      (node (ref "U3") (pin "4") (pinfunction "D-_4") (pintype "unspecified"))
      (node (ref "USB1") (pin "A7") (pinfunction "DN1_A7") (pintype "input"))
      (node (ref "USB1") (pin "B7") (pinfunction "DN2_B7") (pintype "input"))
    )
    (net (code "81") (name "USB_DP") (class "Default")
      (node (ref "U3") (pin "3") (pinfunction "D+_3") (pintype "unspecified"))
      (node (ref "USB1") (pin "A6") (pinfunction "DP1_A6") (pintype "input"))
      (node (ref "USB1") (pin "B6") (pinfunction "DP2_B6") (pintype "input"))
    )
    (net (code "82") (name "VBAT") (class "Default")
      (node (ref "C13") (pin "1") (pinfunction "1_1") (pintype "input"))
      (node (ref "C15") (pin "2") (pinfunction "2_2") (pintype "input"))
      (node (ref "C16") (pin "2") (pinfunction "2_2") (pintype "input"))
      (node (ref "CN1") (pin "1") (pinfunction "1_1") (pintype "unspecified"))
      (node (ref "U13") (pin "3") (pinfunction "VBAT_3") (pintype "input"))
      (node (ref "U15") (pin "1") (pinfunction "IN_1") (pintype "unspecified"))
      (node (ref "U15") (pin "3") (pinfunction "EN_3") (pintype "unspecified"))
    )
    (net (code "83") (name "VBUS") (class "Default")
      (node (ref "C14") (pin "1") (pinfunction "1_1") (pintype "input"))
      (node (ref "R19") (pin "1") (pinfunction "1_1") (pintype "input"))
      (node (ref "U13") (pin "4") (pinfunction "VDD_4") (pintype "input"))
      (node (ref "U3") (pin "7") (pinfunction "VREGIN_7") (pintype "unspecified"))
      (node (ref "U3") (pin "8") (pinfunction "VBUS_8") (pintype "unspecified"))
      (node (ref "USB1") (pin "A4") (pinfunction "VBUS_A4") (pintype "input"))
      (node (ref "USB1") (pin "A9") (pinfunction "VBUS_A9") (pintype "input"))
      (node (ref "USB1") (pin "B4") (pinfunction "VBUS_B4") (pintype "input"))
      (node (ref "USB1") (pin "B9") (pinfunction "VBUS_B9") (pintype "input"))
    )
    (net (code "84") (name "unconnected-(U3-CTS-Pad18)") (class "Default")
      (node (ref "U3") (pin "18") (pinfunction "CTS_18") (pintype "unspecified+no_connect"))
    )
    (net (code "85") (name "unconnected-(U3-DCD-Pad24)") (class "Default")
      (node (ref "U3") (pin "24") (pinfunction "DCD_24") (pintype "unspecified+no_connect"))
    )
    (net (code "86") (name "unconnected-(U3-DSR-Pad22)") (class "Default")
      (node (ref "U3") (pin "22") (pinfunction "DSR_22") (pintype "unspecified+no_connect"))
    )
    (net (code "87") (name "unconnected-(U3-DTR-Pad23)") (class "Default")
      (node (ref "U3") (pin "23") (pinfunction "DTR_23") (pintype "unspecified+no_connect"))
    )
    (net (code "88") (name "unconnected-(U3-GPIO.0{slash}TXT-Pad14)") (class "Default")
      (node (ref "U3") (pin "14") (pinfunction "GPIO.0/TXT_14") (pintype "unspecified+no_connect"))
    )
    (net (code "89") (name "unconnected-(U3-GPIO.1{slash}RXT-Pad13)") (class "Default")
      (node (ref "U3") (pin "13") (pinfunction "GPIO.1/RXT_13") (pintype "unspecified+no_connect"))
    )
    (net (code "90") (name "unconnected-(U3-GPIO.2{slash}RS485-Pad12)") (class "Default")
      (node (ref "U3") (pin "12") (pinfunction "GPIO.2/RS485_12") (pintype "unspecified+no_connect"))
    )
    (net (code "91") (name "unconnected-(U3-GPIO.3{slash}WAKEUP-Pad11)") (class "Default")
      (node (ref "U3") (pin "11") (pinfunction "GPIO.3/WAKEUP_11") (pintype "unspecified+no_connect"))
    )
    (net (code "92") (name "unconnected-(U3-NC-Pad10)") (class "Default")
      (node (ref "U3") (pin "10") (pinfunction "NC_10") (pintype "unspecified+no_connect"))
    )
    (net (code "93") (name "unconnected-(U3-NC-Pad16)") (class "Default")
      (node (ref "U3") (pin "16") (pinfunction "NC_16") (pintype "unspecified+no_connect"))
    )
    (net (code "94") (name "unconnected-(U3-RI{slash}CLK-Pad1)") (class "Default")
      (node (ref "U3") (pin "1") (pinfunction "RI/CLK_1") (pintype "unspecified+no_connect"))
    )
    (net (code "95") (name "unconnected-(U3-RTS-Pad19)") (class "Default")
      (node (ref "U3") (pin "19") (pinfunction "RTS_19") (pintype "unspecified+no_connect"))
    )
    (net (code "96") (name "unconnected-(U3-SUSPEND-Pad17)") (class "Default")
      (node (ref "U3") (pin "17") (pinfunction "SUSPEND_17") (pintype "unspecified+no_connect"))
    )
    (net (code "97") (name "unconnected-(U3-SUSPENDb-Pad15)") (class "Default")
      (node (ref "U3") (pin "15") (pinfunction "SUSPENDb_15") (pintype "unspecified+no_connect"))
    )
    (net (code "98") (name "unconnected-(U5-NC-Pad3)") (class "Default")
      (node (ref "U5") (pin "3") (pinfunction "NC_3") (pintype "unspecified+no_connect"))
    )
    (net (code "99") (name "unconnected-(U5-NC-Pad4)") (class "Default")
      (node (ref "U5") (pin "4") (pinfunction "NC_4") (pintype "unspecified+no_connect"))
    )
    (net (code "100") (name "unconnected-(U6-n{slash}a-Pad4)") (class "Default")
      (node (ref "U6") (pin "4") (pinfunction "n/a_4") (pintype "unspecified+no_connect"))
    )
    (net (code "101") (name "unconnected-(U10-PC13-TAMPER-RTC-Pad2)") (class "Default")
      (node (ref "U10") (pin "2") (pinfunction "PC13-TAMPER-RTC_2") (pintype "unspecified+no_connect"))
    )
    (net (code "102") (name "unconnected-(U10-PD0-OSCIN-Pad5)") (class "Default")
      (node (ref "U10") (pin "5") (pinfunction "PD0-OSCIN_5") (pintype "unspecified+no_connect"))
    )
    (net (code "103") (name "unconnected-(U10-PD1-OSCOUT-Pad6)") (class "Default")
      (node (ref "U10") (pin "6") (pinfunction "PD1-OSCOUT_6") (pintype "unspecified+no_connect"))
    )
    (net (code "104") (name "unconnected-(U11-NC-Pad20)") (class "Default")
      (node (ref "U11") (pin "20") (pinfunction "NC_20") (pintype "input+no_connect"))
    )
    (net (code "105") (name "unconnected-(U11-P00-Pad6)") (class "Default")
      (node (ref "U11") (pin "6") (pinfunction "P00_6") (pintype "input+no_connect"))
    )
    (net (code "106") (name "unconnected-(U15-NC-Pad4)") (class "Default")
      (node (ref "U15") (pin "4") (pinfunction "NC_4") (pintype "unspecified+no_connect"))
    )
    (net (code "107") (name "unconnected-(USB1-SBUS1-PadA8)") (class "Default")
      (node (ref "USB1") (pin "A8") (pinfunction "SBUS1_A8") (pintype "input+no_connect"))
    )
    (net (code "108") (name "unconnected-(USB1-SBUS2-PadB8)") (class "Default")
      (node (ref "USB1") (pin "B8") (pinfunction "SBUS2_B8") (pintype "input+no_connect"))
    )
  )
)
